# V2_0.net
KiCad netlist of a schematic drawn in Altium Designer
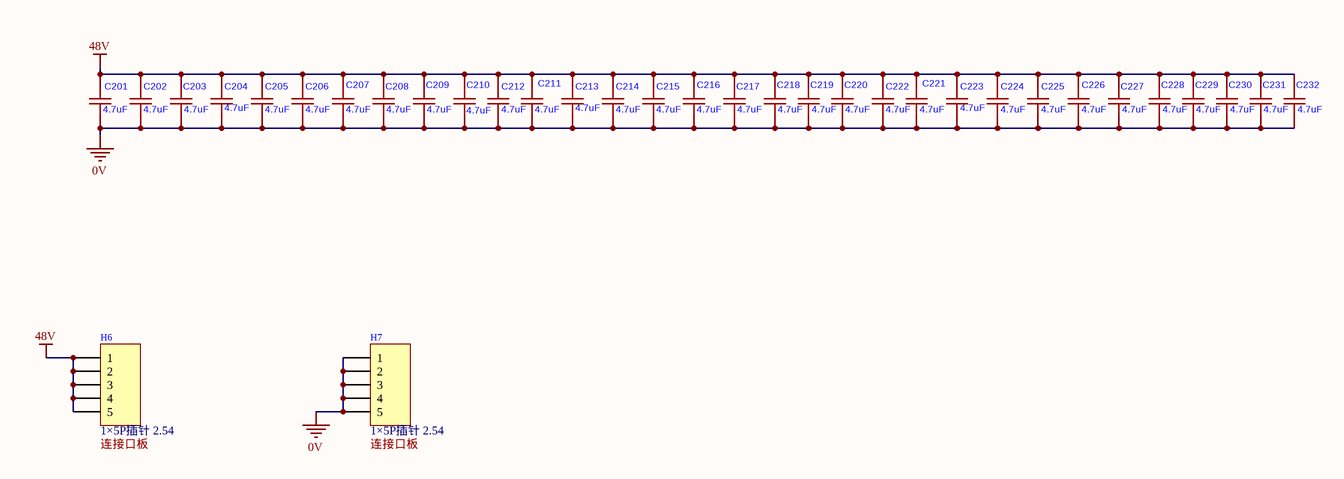
[diagram p0: 原理图V2.0.SchDoc]

(export (version "E")
  (design (tool "Eeschema 10.0.6"))
  (components
    (comp (ref "C201")
      (value "4.7uF")
      (footprint "1210_C")
      (description "100V 4.7uf 1210")
      (fields (field (name "MANUFACTURER") "FH(风华)") (field (name "MANUFACTURER PART") "1210B475K101NT"))
      (libsource (lib "Schlib1") (part "1210 4.7uf"))
    )
    (comp (ref "C202")
      (value "4.7uF")
      (footprint "1210_C")
      (description "100V 4.7uf 1210")
      (fields (field (name "MANUFACTURER") "FH(风华)") (field (name "MANUFACTURER PART") "1210B475K101NT"))
      (libsource (lib "Schlib1") (part "1210 4.7uf"))
    )
    (comp (ref "C203")
      (value "4.7uF")
      (footprint "1210_C")
      (description "100V 4.7uf 1210")
      (fields (field (name "MANUFACTURER") "FH(风华)") (field (name "MANUFACTURER PART") "1210B475K101NT"))
      (libsource (lib "Schlib1") (part "1210 4.7uf"))
    )
    (comp (ref "C204")
      (value "4.7uF")
      (footprint "1210_C")
      (description "100V 4.7uf 1210")
      (fields (field (name "MANUFACTURER") "FH(风华)") (field (name "MANUFACTURER PART") "1210B475K101NT"))
      (libsource (lib "Schlib1") (part "1210 4.7uf"))
    )
    (comp (ref "C205")
      (value "4.7uF")
      (footprint "1210_C")
      (description "100V 4.7uf 1210")
      (fields (field (name "MANUFACTURER") "FH(风华)") (field (name "MANUFACTURER PART") "1210B475K101NT"))
      (libsource (lib "Schlib1") (part "1210 4.7uf"))
    )
    (comp (ref "C206")
      (value "4.7uF")
      (footprint "1210_C")
      (description "100V 4.7uf 1210")
      (fields (field (name "MANUFACTURER") "FH(风华)") (field (name "MANUFACTURER PART") "1210B475K101NT"))
      (libsource (lib "Schlib1") (part "1210 4.7uf"))
    )
    (comp (ref "C207")
      (value "4.7uF")
      (footprint "1210_C")
      (description "100V 4.7uf 1210")
      (fields (field (name "MANUFACTURER") "FH(风华)") (field (name "MANUFACTURER PART") "1210B475K101NT"))
      (libsource (lib "Schlib1") (part "1210 4.7uf"))
    )
    (comp (ref "C208")
      (value "4.7uF")
      (footprint "1210_C")
      (description "100V 4.7uf 1210")
      (fields (field (name "MANUFACTURER") "FH(风华)") (field (name "MANUFACTURER PART") "1210B475K101NT"))
      (libsource (lib "Schlib1") (part "1210 4.7uf"))
    )
    (comp (ref "C209")
      (value "4.7uF")
      (footprint "1210_C")
      (description "100V 4.7uf 1210")
      (fields (field (name "MANUFACTURER") "FH(风华)") (field (name "MANUFACTURER PART") "1210B475K101NT"))
      (libsource (lib "Schlib1") (part "1210 4.7uf"))
    )
    (comp (ref "C210")
      (value "4.7uF")
      (footprint "1210_C")
      (description "100V 4.7uf 1210")
      (fields (field (name "MANUFACTURER") "FH(风华)") (field (name "MANUFACTURER PART") "1210B475K101NT"))
      (libsource (lib "Schlib1") (part "1210 4.7uf"))
    )
    (comp (ref "C211")
      (value "4.7uF")
      (footprint "1210_C")
      (description "100V 4.7uf 1210")
      (fields (field (name "MANUFACTURER") "FH(风华)") (field (name "MANUFACTURER PART") "1210B475K101NT"))
      (libsource (lib "Schlib1") (part "1210 4.7uf"))
    )
    (comp (ref "C212")
      (value "4.7uF")
      (footprint "1210_C")
      (description "100V 4.7uf 1210")
      (fields (field (name "MANUFACTURER") "FH(风华)") (field (name "MANUFACTURER PART") "1210B475K101NT"))
      (libsource (lib "Schlib1") (part "1210 4.7uf"))
    )
    (comp (ref "C213")
      (value "4.7uF")
      (footprint "1210_C")
      (description "100V 4.7uf 1210")
      (fields (field (name "MANUFACTURER") "FH(风华)") (field (name "MANUFACTURER PART") "1210B475K101NT"))
      (libsource (lib "Schlib1") (part "1210 4.7uf"))
    )
    (comp (ref "C214")
      (value "4.7uF")
      (footprint "1210_C")
      (description "100V 4.7uf 1210")
      (fields (field (name "MANUFACTURER") "FH(风华)") (field (name "MANUFACTURER PART") "1210B475K101NT"))
      (libsource (lib "Schlib1") (part "1210 4.7uf"))
    )
    (comp (ref "C215")
      (value "4.7uF")
      (footprint "1210_C")
      (description "100V 4.7uf 1210")
      (fields (field (name "MANUFACTURER") "FH(风华)") (field (name "MANUFACTURER PART") "1210B475K101NT"))
      (libsource (lib "Schlib1") (part "1210 4.7uf"))
    )
    (comp (ref "C216")
      (value "4.7uF")
      (footprint "1210_C")
      (description "100V 4.7uf 1210")
      (fields (field (name "MANUFACTURER") "FH(风华)") (field (name "MANUFACTURER PART") "1210B475K101NT"))
      (libsource (lib "Schlib1") (part "1210 4.7uf"))
    )
    (comp (ref "C217")
      (value "4.7uF")
      (footprint "1210_C")
      (description "100V 4.7uf 1210")
      (fields (field (name "MANUFACTURER") "FH(风华)") (field (name "MANUFACTURER PART") "1210B475K101NT"))
      (libsource (lib "Schlib1") (part "1210 4.7uf"))
    )
    (comp (ref "C218")
      (value "4.7uF")
      (footprint "1210_C")
      (description "100V 4.7uf 1210")
      (fields (field (name "MANUFACTURER") "FH(风华)") (field (name "MANUFACTURER PART") "1210B475K101NT"))
      (libsource (lib "Schlib1") (part "1210 4.7uf"))
    )
    (comp (ref "C219")
      (value "4.7uF")
      (footprint "1210_C")
      (description "100V 4.7uf 1210")
      (fields (field (name "MANUFACTURER") "FH(风华)") (field (name "MANUFACTURER PART") "1210B475K101NT"))
      (libsource (lib "Schlib1") (part "1210 4.7uf"))
    )
    (comp (ref "C220")
      (value "4.7uF")
      (footprint "1210_C")
      (description "100V 4.7uf 1210")
      (fields (field (name "MANUFACTURER") "FH(风华)") (field (name "MANUFACTURER PART") "1210B475K101NT"))
      (libsource (lib "Schlib1") (part "1210 4.7uf"))
    )
    (comp (ref "C221")
      (value "4.7uF")
      (footprint "1210_C")
      (description "100V 4.7uf 1210")
      (fields (field (name "MANUFACTURER") "FH(风华)") (field (name "MANUFACTURER PART") "1210B475K101NT"))
      (libsource (lib "Schlib1") (part "1210 4.7uf"))
    )
    (comp (ref "C222")
      (value "4.7uF")
      (footprint "1210_C")
      (description "100V 4.7uf 1210")
      (fields (field (name "MANUFACTURER") "FH(风华)") (field (name "MANUFACTURER PART") "1210B475K101NT"))
      (libsource (lib "Schlib1") (part "1210 4.7uf"))
    )
    (comp (ref "C223")
      (value "4.7uF")
      (footprint "1210_C")
      (description "100V 4.7uf 1210")
      (fields (field (name "MANUFACTURER") "FH(风华)") (field (name "MANUFACTURER PART") "1210B475K101NT"))
      (libsource (lib "Schlib1") (part "1210 4.7uf"))
    )
    (comp (ref "C224")
      (value "4.7uF")
      (footprint "1210_C")
      (description "100V 4.7uf 1210")
      (fields (field (name "MANUFACTURER") "FH(风华)") (field (name "MANUFACTURER PART") "1210B475K101NT"))
      (libsource (lib "Schlib1") (part "1210 4.7uf"))
    )
    (comp (ref "C225")
      (value "4.7uF")
      (footprint "1210_C")
      (description "100V 4.7uf 1210")
      (fields (field (name "MANUFACTURER") "FH(风华)") (field (name "MANUFACTURER PART") "1210B475K101NT"))
      (libsource (lib "Schlib1") (part "1210 4.7uf"))
    )
    (comp (ref "C226")
      (value "4.7uF")
      (footprint "1210_C")
      (description "100V 4.7uf 1210")
      (fields (field (name "MANUFACTURER") "FH(风华)") (field (name "MANUFACTURER PART") "1210B475K101NT"))
      (libsource (lib "Schlib1") (part "1210 4.7uf"))
    )
    (comp (ref "C227")
      (value "4.7uF")
      (footprint "1210_C")
      (description "100V 4.7uf 1210")
      (fields (field (name "MANUFACTURER") "FH(风华)") (field (name "MANUFACTURER PART") "1210B475K101NT"))
      (libsource (lib "Schlib1") (part "1210 4.7uf"))
    )
    (comp (ref "C228")
      (value "4.7uF")
      (footprint "1210_C")
      (description "100V 4.7uf 1210")
      (fields (field (name "MANUFACTURER") "FH(风华)") (field (name "MANUFACTURER PART") "1210B475K101NT"))
      (libsource (lib "Schlib1") (part "1210 4.7uf"))
    )
    (comp (ref "C229")
      (value "4.7uF")
      (footprint "1210_C")
      (description "100V 4.7uf 1210")
      (fields (field (name "MANUFACTURER") "FH(风华)") (field (name "MANUFACTURER PART") "1210B475K101NT"))
      (libsource (lib "Schlib1") (part "1210 4.7uf"))
    )
    (comp (ref "C230")
      (value "4.7uF")
      (footprint "1210_C")
      (description "100V 4.7uf 1210")
      (fields (field (name "MANUFACTURER") "FH(风华)") (field (name "MANUFACTURER PART") "1210B475K101NT"))
      (libsource (lib "Schlib1") (part "1210 4.7uf"))
    )
    (comp (ref "C231")
      (value "4.7uF")
      (footprint "1210_C")
      (description "100V 4.7uf 1210")
      (fields (field (name "MANUFACTURER") "FH(风华)") (field (name "MANUFACTURER PART") "1210B475K101NT"))
      (libsource (lib "Schlib1") (part "1210 4.7uf"))
    )
    (comp (ref "C232")
      (value "4.7uF")
      (footprint "1210_C")
      (description "100V 4.7uf 1210")
      (fields (field (name "MANUFACTURER") "FH(风华)") (field (name "MANUFACTURER PART") "1210B475K101NT"))
      (libsource (lib "Schlib1") (part "1210 4.7uf"))
    )
    (comp (ref "H6")
      (value "1×5P插针 2.54")
      (footprint "HDR1X5")
      (description "Header, 5-Pin")
      (fields (field (name "PUBLISHER") "Altium Limited"))
      (libsource (lib "Miscellaneous Connectors") (part "Header 5"))
    )
    (comp (ref "H7")
      (value "1×5P插针 2.54")
      (footprint "HDR1X5")
      (description "Header, 5-Pin")
      (fields (field (name "PUBLISHER") "Altium Limited"))
      (libsource (lib "Miscellaneous Connectors") (part "Header 5"))
    )
  )
  (nets
    (net (code "1") (name "0V") (class "Default")
      (node (ref "C201") (pin "1") (pinfunction "1_1") (pintype "passive"))
      (node (ref "C202") (pin "1") (pinfunction "1_1") (pintype "passive"))
      (node (ref "C203") (pin "1") (pinfunction "1_1") (pintype "passive"))
      (node (ref "C204") (pin "1") (pinfunction "1_1") (pintype "passive"))
      (node (ref "C205") (pin "1") (pinfunction "1_1") (pintype "passive"))
      (node (ref "C206") (pin "1") (pinfunction "1_1") (pintype "passive"))
      (node (ref "C207") (pin "1") (pinfunction "1_1") (pintype "passive"))
      (node (ref "C208") (pin "1") (pinfunction "1_1") (pintype "passive"))
      (node (ref "C209") (pin "1") (pinfunction "1_1") (pintype "passive"))
      (node (ref "C210") (pin "1") (pinfunction "1_1") (pintype "passive"))
      (node (ref "C211") (pin "1") (pinfunction "1_1") (pintype "passive"))
      (node (ref "C212") (pin "1") (pinfunction "1_1") (pintype "passive"))
      (node (ref "C213") (pin "1") (pinfunction "1_1") (pintype "passive"))
      (node (ref "C214") (pin "1") (pinfunction "1_1") (pintype "passive"))
      (node (ref "C215") (pin "1") (pinfunction "1_1") (pintype "passive"))
      (node (ref "C216") (pin "1") (pinfunction "1_1") (pintype "passive"))
      (node (ref "C217") (pin "1") (pinfunction "1_1") (pintype "passive"))
      (node (ref "C218") (pin "1") (pinfunction "1_1") (pintype "passive"))
      (node (ref "C219") (pin "1") (pinfunction "1_1") (pintype "passive"))
      (node (ref "C220") (pin "1") (pinfunction "1_1") (pintype "passive"))
      (node (ref "C221") (pin "1") (pinfunction "1_1") (pintype "passive"))
      (node (ref "C222") (pin "1") (pinfunction "1_1") (pintype "passive"))
      (node (ref "C223") (pin "1") (pinfunction "1_1") (pintype "passive"))
      (node (ref "C224") (pin "1") (pinfunction "1_1") (pintype "passive"))
      (node (ref "C225") (pin "1") (pinfunction "1_1") (pintype "passive"))
      (node (ref "C226") (pin "1") (pinfunction "1_1") (pintype "passive"))
      (node (ref "C227") (pin "1") (pinfunction "1_1") (pintype "passive"))
      (node (ref "C228") (pin "1") (pinfunction "1_1") (pintype "passive"))
      (node (ref "C229") (pin "1") (pinfunction "1_1") (pintype "passive"))
      (node (ref "C230") (pin "1") (pinfunction "1_1") (pintype "passive"))
      (node (ref "C231") (pin "1") (pinfunction "1_1") (pintype "passive"))
      (node (ref "C232") (pin "1") (pinfunction "1_1") (pintype "passive"))
      (node (ref "H7") (pin "1") (pinfunction "1_1") (pintype "passive"))
      (node (ref "H7") (pin "2") (pinfunction "2_2") (pintype "passive"))
      (node (ref "H7") (pin "3") (pinfunction "3_3") (pintype "passive"))
      (node (ref "H7") (pin "4") (pinfunction "4_4") (pintype "passive"))
      (node (ref "H7") (pin "5") (pinfunction "5_5") (pintype "passive"))
    )
    (net (code "2") (name "48V") (class "Default")
      (node (ref "C201") (pin "2") (pinfunction "2_2") (pintype "passive"))
      (node (ref "C202") (pin "2") (pinfunction "2_2") (pintype "passive"))
      (node (ref "C203") (pin "2") (pinfunction "2_2") (pintype "passive"))
      (node (ref "C204") (pin "2") (pinfunction "2_2") (pintype "passive"))
      (node (ref "C205") (pin "2") (pinfunction "2_2") (pintype "passive"))
      (node (ref "C206") (pin "2") (pinfunction "2_2") (pintype "passive"))
      (node (ref "C207") (pin "2") (pinfunction "2_2") (pintype "passive"))
      (node (ref "C208") (pin "2") (pinfunction "2_2") (pintype "passive"))
      (node (ref "C209") (pin "2") (pinfunction "2_2") (pintype "passive"))
      (node (ref "C210") (pin "2") (pinfunction "2_2") (pintype "passive"))
      (node (ref "C211") (pin "2") (pinfunction "2_2") (pintype "passive"))
      (node (ref "C212") (pin "2") (pinfunction "2_2") (pintype "passive"))
      (node (ref "C213") (pin "2") (pinfunction "2_2") (pintype "passive"))
      (node (ref "C214") (pin "2") (pinfunction "2_2") (pintype "passive"))
      (node (ref "C215") (pin "2") (pinfunction "2_2") (pintype "passive"))
      (node (ref "C216") (pin "2") (pinfunction "2_2") (pintype "passive"))
      (node (ref "C217") (pin "2") (pinfunction "2_2") (pintype "passive"))
      (node (ref "C218") (pin "2") (pinfunction "2_2") (pintype "passive"))
      (node (ref "C219") (pin "2") (pinfunction "2_2") (pintype "passive"))
      (node (ref "C220") (pin "2") (pinfunction "2_2") (pintype "passive"))
      (node (ref "C221") (pin "2") (pinfunction "2_2") (pintype "passive"))
      (node (ref "C222") (pin "2") (pinfunction "2_2") (pintype "passive"))
      (node (ref "C223") (pin "2") (pinfunction "2_2") (pintype "passive"))
      (node (ref "C224") (pin "2") (pinfunction "2_2") (pintype "passive"))
      (node (ref "C225") (pin "2") (pinfunction "2_2") (pintype "passive"))
      (node (ref "C226") (pin "2") (pinfunction "2_2") (pintype "passive"))
      (node (ref "C227") (pin "2") (pinfunction "2_2") (pintype "passive"))
      (node (ref "C228") (pin "2") (pinfunction "2_2") (pintype "passive"))
      (node (ref "C229") (pin "2") (pinfunction "2_2") (pintype "passive"))
      (node (ref "C230") (pin "2") (pinfunction "2_2") (pintype "passive"))
      (node (ref "C231") (pin "2") (pinfunction "2_2") (pintype "passive"))
      (node (ref "C232") (pin "2") (pinfunction "2_2") (pintype "passive"))
      (node (ref "H6") (pin "1") (pinfunction "1_1") (pintype "passive"))
      (node (ref "H6") (pin "2") (pinfunction "2_2") (pintype "passive"))
      (node (ref "H6") (pin "3") (pinfunction "3_3") (pintype "passive"))
      (node (ref "H6") (pin "4") (pinfunction "4_4") (pintype "passive"))
      (node (ref "H6") (pin "5") (pinfunction "5_5") (pintype "passive"))
    )
  )
)
